# analog.net
KiCad netlist of a schematic drawn in Altium Designer
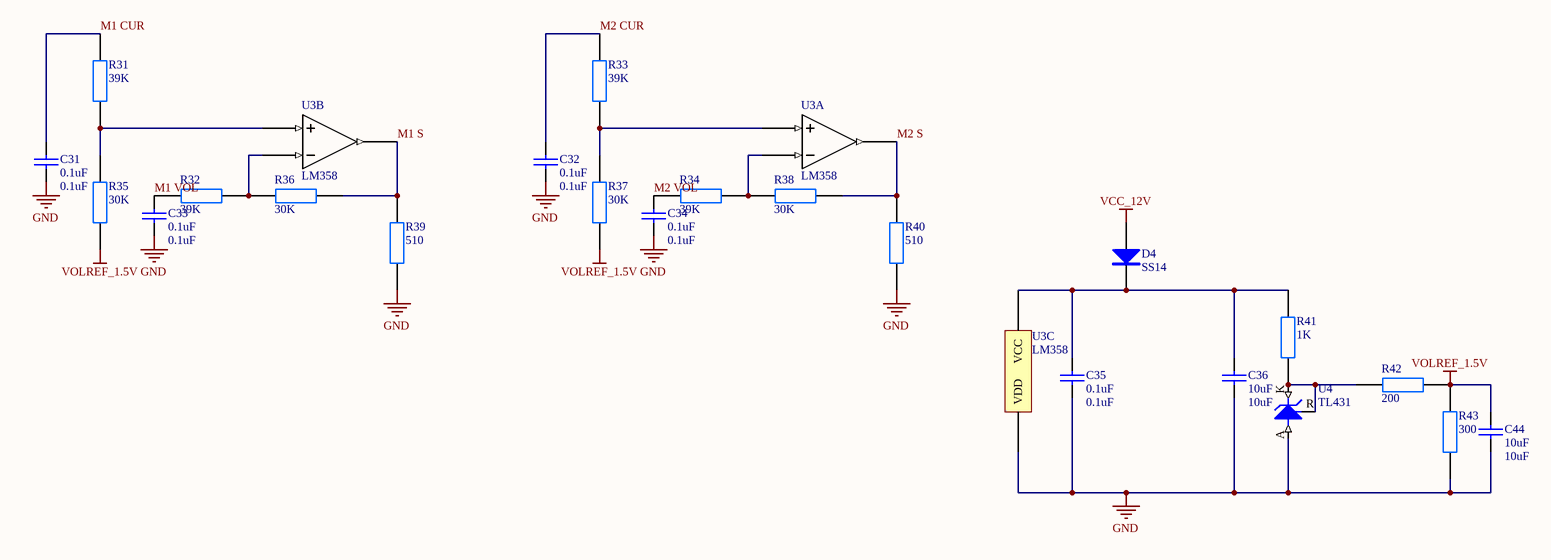
[diagram p0: analog.SchDoc]

(export (version "E")
  (design (tool "Eeschema 10.0.6"))
  (components
    (comp (ref "C31")
      (value "0.1uF")
      (footprint "0805 CAP")
      (fields (field (name "ALTIUM_VALUE") "0.1uF"))
      (libsource (lib "common") (part "CAP"))
    )
    (comp (ref "C32")
      (value "0.1uF")
      (footprint "0805 CAP")
      (fields (field (name "ALTIUM_VALUE") "0.1uF"))
      (libsource (lib "common") (part "CAP"))
    )
    (comp (ref "C33")
      (value "0.1uF")
      (footprint "0805 CAP")
      (fields (field (name "ALTIUM_VALUE") "0.1uF"))
      (libsource (lib "common") (part "CAP"))
    )
    (comp (ref "C34")
      (value "0.1uF")
      (footprint "0805 CAP")
      (fields (field (name "ALTIUM_VALUE") "0.1uF"))
      (libsource (lib "common") (part "CAP"))
    )
    (comp (ref "C35")
      (value "0.1uF")
      (footprint "0805 CAP")
      (fields (field (name "ALTIUM_VALUE") "0.1uF"))
      (libsource (lib "common") (part "CAP"))
    )
    (comp (ref "C36")
      (value "10uF")
      (footprint "0805 CAP")
      (fields (field (name "ALTIUM_VALUE") "10uF"))
      (libsource (lib "common") (part "CAP"))
    )
    (comp (ref "C44")
      (value "10uF")
      (footprint "0805 CAP")
      (fields (field (name "ALTIUM_VALUE") "10uF"))
      (libsource (lib "common") (part "CAP"))
    )
    (comp (ref "D4")
      (value "SS14")
      (footprint "SMA")
      (description "Diode")
      (libsource (lib "common") (part "SS14"))
    )
    (comp (ref "R31")
      (value "39K")
      (footprint "0805")
      (description "RES")
      (libsource (lib "common") (part "RES"))
    )
    (comp (ref "R32")
      (value "39K")
      (footprint "0805")
      (description "RES")
      (libsource (lib "common") (part "RES"))
    )
    (comp (ref "R33")
      (value "39K")
      (footprint "0805")
      (description "RES")
      (libsource (lib "common") (part "RES"))
    )
    (comp (ref "R34")
      (value "39K")
      (footprint "0805")
      (description "RES")
      (libsource (lib "common") (part "RES"))
    )
    (comp (ref "R35")
      (value "30K")
      (footprint "0805")
      (description "RES")
      (libsource (lib "common") (part "RES"))
    )
    (comp (ref "R36")
      (value "30K")
      (footprint "0805")
      (description "RES")
      (libsource (lib "common") (part "RES"))
    )
    (comp (ref "R37")
      (value "30K")
      (footprint "0805")
      (description "RES")
      (libsource (lib "common") (part "RES"))
    )
    (comp (ref "R38")
      (value "30K")
      (footprint "0805")
      (description "RES")
      (libsource (lib "common") (part "RES"))
    )
    (comp (ref "R39")
      (value "510")
      (footprint "0805")
      (description "RES")
      (libsource (lib "common") (part "RES"))
    )
    (comp (ref "R40")
      (value "510")
      (footprint "0805")
      (description "RES")
      (libsource (lib "common") (part "RES"))
    )
    (comp (ref "R41")
      (value "1K")
      (footprint "0805")
      (description "RES")
      (libsource (lib "common") (part "RES"))
    )
    (comp (ref "R42")
      (value "200")
      (footprint "0805")
      (description "RES")
      (libsource (lib "common") (part "RES"))
    )
    (comp (ref "R43")
      (value "300")
      (footprint "0805")
      (description "RES")
      (libsource (lib "common") (part "RES"))
    )
    (comp (ref "U3") (value "LM358") (footprint "so-8") (libsource (lib "common") (part "LM358")))
    (comp (ref "U4")
      (value "TL431")
      (footprint "sot-23")
      (description "IC")
      (libsource (lib "common") (part "TL431"))
    )
  )
  (nets
    (net (code "1") (name "/M1 CUR") (class "Default")
      (node (ref "C31") (pin "1") (pinfunction "1_1") (pintype "passive"))
      (node (ref "R31") (pin "2") (pinfunction "2_2") (pintype "passive"))
    )
    (net (code "2") (name "/M1 S") (class "Default")
      (node (ref "R36") (pin "1") (pinfunction "1_1") (pintype "passive"))
      (node (ref "R39") (pin "2") (pinfunction "2_2") (pintype "passive"))
      (node (ref "U3") (pin "7") (pinfunction "7_7") (pintype "output"))
    )
    (net (code "3") (name "/M1 VOL") (class "Default")
      (node (ref "C33") (pin "1") (pinfunction "1_1") (pintype "passive"))
      (node (ref "R32") (pin "2") (pinfunction "2_2") (pintype "passive"))
    )
    (net (code "4") (name "/M2 CUR") (class "Default")
      (node (ref "C32") (pin "1") (pinfunction "1_1") (pintype "passive"))
      (node (ref "R33") (pin "2") (pinfunction "2_2") (pintype "passive"))
    )
    (net (code "5") (name "/M2 S") (class "Default")
      (node (ref "R38") (pin "1") (pinfunction "1_1") (pintype "passive"))
      (node (ref "R40") (pin "2") (pinfunction "2_2") (pintype "passive"))
      (node (ref "U3") (pin "1") (pinfunction "1_1") (pintype "output"))
    )
    (net (code "6") (name "/M2 VOL") (class "Default")
      (node (ref "C34") (pin "1") (pinfunction "1_1") (pintype "passive"))
      (node (ref "R34") (pin "2") (pinfunction "2_2") (pintype "passive"))
    )
    (net (code "7") (name "GND") (class "Default")
      (node (ref "C31") (pin "2") (pinfunction "2_2") (pintype "passive"))
      (node (ref "C32") (pin "2") (pinfunction "2_2") (pintype "passive"))
      (node (ref "C33") (pin "2") (pinfunction "2_2") (pintype "passive"))
      (node (ref "C34") (pin "2") (pinfunction "2_2") (pintype "passive"))
      (node (ref "C35") (pin "2") (pinfunction "2_2") (pintype "passive"))
      (node (ref "C36") (pin "2") (pinfunction "2_2") (pintype "passive"))
      (node (ref "C44") (pin "2") (pinfunction "2_2") (pintype "passive"))
      (node (ref "R39") (pin "1") (pinfunction "1_1") (pintype "passive"))
      (node (ref "R40") (pin "1") (pinfunction "1_1") (pintype "passive"))
      (node (ref "R43") (pin "1") (pinfunction "1_1") (pintype "passive"))
      (node (ref "U3") (pin "4") (pinfunction "VDD_4") (pintype "power_in"))
      (node (ref "U4") (pin "A") (pinfunction "A_A") (pintype "input"))
    )
    (net (code "8") (name "Net-(D4-K)") (class "Default")
      (node (ref "C35") (pin "1") (pinfunction "1_1") (pintype "passive"))
      (node (ref "C36") (pin "1") (pinfunction "1_1") (pintype "passive"))
      (node (ref "D4") (pin "2") (pinfunction "K_2") (pintype "passive"))
      (node (ref "R41") (pin "2") (pinfunction "2_2") (pintype "passive"))
      (node (ref "U3") (pin "8") (pinfunction "VCC_8") (pintype "power_in"))
    )
    (net (code "9") (name "Net-(R31-Pad1)") (class "Default")
      (node (ref "R31") (pin "1") (pinfunction "1_1") (pintype "passive"))
      (node (ref "R35") (pin "2") (pinfunction "2_2") (pintype "passive"))
      (node (ref "U3") (pin "5") (pinfunction "5_5") (pintype "input"))
    )
    (net (code "10") (name "Net-(R32-Pad1)") (class "Default")
      (node (ref "R32") (pin "1") (pinfunction "1_1") (pintype "passive"))
      (node (ref "R36") (pin "2") (pinfunction "2_2") (pintype "passive"))
      (node (ref "U3") (pin "6") (pinfunction "6_6") (pintype "input"))
    )
    (net (code "11") (name "Net-(R33-Pad1)") (class "Default")
      (node (ref "R33") (pin "1") (pinfunction "1_1") (pintype "passive"))
      (node (ref "R37") (pin "2") (pinfunction "2_2") (pintype "passive"))
      (node (ref "U3") (pin "3") (pinfunction "3_3") (pintype "input"))
    )
    (net (code "12") (name "Net-(R34-Pad1)") (class "Default")
      (node (ref "R34") (pin "1") (pinfunction "1_1") (pintype "passive"))
      (node (ref "R38") (pin "2") (pinfunction "2_2") (pintype "passive"))
      (node (ref "U3") (pin "2") (pinfunction "2_2") (pintype "input"))
    )
    (net (code "13") (name "Net-(R41-Pad1)") (class "Default")
      (node (ref "R41") (pin "1") (pinfunction "1_1") (pintype "passive"))
      (node (ref "R42") (pin "2") (pinfunction "2_2") (pintype "passive"))
      (node (ref "U4") (pin "K") (pinfunction "K_K") (pintype "input"))
      (node (ref "U4") (pin "R") (pinfunction "R_R") (pintype "passive"))
    )
    (net (code "14") (name "VCC_12V") (class "Default")
      (node (ref "D4") (pin "1") (pinfunction "A_1") (pintype "passive"))
    )
    (net (code "15") (name "VOLREF_1.5V") (class "Default")
      (node (ref "C44") (pin "1") (pinfunction "1_1") (pintype "passive"))
      (node (ref "R35") (pin "1") (pinfunction "1_1") (pintype "passive"))
      (node (ref "R37") (pin "1") (pinfunction "1_1") (pintype "passive"))
      (node (ref "R42") (pin "1") (pinfunction "1_1") (pintype "passive"))
      (node (ref "R43") (pin "2") (pinfunction "2_2") (pintype "passive"))
    )
  )
)
